# Output_Driver.net
KiCad netlist of a schematic drawn in Altium Designer
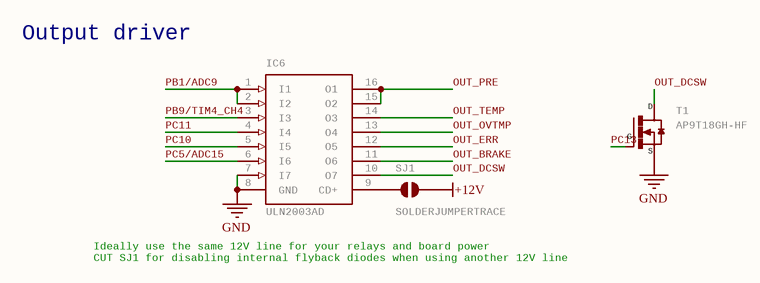
[diagram p0: Output Driver.SchDoc]

(export (version "E")
  (design (tool "Eeschema 10.0.6"))
  (components
    (comp (ref "IC6")
      (value "ULN2003AD")
      (footprint "SO16")
      (description "DRIVER ARRAY")
      (fields (field (name "LIBRARYNAME") "uln-udn"))
      (libsource (lib "Gate Driver Board") (part "ULN2003AD"))
    )
    (comp (ref "SJ1")
      (value "SOLDERJUMPERTRACE")
      (footprint "SJ_2S-TRACE")
      (libsource (lib "SparkFun-Passives") (part "SOLDERJUMPERTRACE"))
    )
    (comp (ref "T1")
      (value "AP9T18GH-HF")
      (footprint "D-PAK_TO252AA")
      (fields (field (name "D") "D") (field (name "S") "S") (field (name "G") "G"))
      (libsource (lib "Gate Driver Board") (part "AP9T18GH-HF"))
    )
  )
  (nets
    (net (code "1") (name "+12V") (class "Default")
      (node (ref "SJ1") (pin "2") (pinfunction "2_2") (pintype "passive"))
    )
    (net (code "2") (name "/OUT_BRAKE") (class "Default")
      (node (ref "IC6") (pin "11") (pinfunction "O6_11") (pintype "open_collector"))
    )
    (net (code "3") (name "/OUT_DCSW") (class "Default")
      (node (ref "IC6") (pin "10") (pinfunction "O7_10") (pintype "open_collector"))
      (node (ref "T1") (pin "4") (pinfunction "D_4") (pintype "passive"))
    )
    (net (code "4") (name "/OUT_ERR") (class "Default")
      (node (ref "IC6") (pin "12") (pinfunction "O5_12") (pintype "open_collector"))
    )
    (net (code "5") (name "/OUT_OVTMP") (class "Default")
      (node (ref "IC6") (pin "13") (pinfunction "O4_13") (pintype "open_collector"))
    )
    (net (code "6") (name "/OUT_PRE") (class "Default")
      (node (ref "IC6") (pin "15") (pinfunction "O2_15") (pintype "open_collector"))
      (node (ref "IC6") (pin "16") (pinfunction "O1_16") (pintype "open_collector"))
    )
    (net (code "7") (name "/OUT_TEMP") (class "Default")
      (node (ref "IC6") (pin "14") (pinfunction "O3_14") (pintype "open_collector"))
    )
    (net (code "8") (name "/PB1{slash}ADC9") (class "Default")
      (node (ref "IC6") (pin "1") (pinfunction "I1_1") (pintype "input"))
      (node (ref "IC6") (pin "2") (pinfunction "I2_2") (pintype "input"))
    )
    (net (code "9") (name "/PB9{slash}TIM4_CH4") (class "Default")
      (node (ref "IC6") (pin "3") (pinfunction "I3_3") (pintype "input"))
    )
    (net (code "10") (name "/PC5{slash}ADC15") (class "Default")
      (node (ref "IC6") (pin "6") (pinfunction "I6_6") (pintype "input"))
    )
    (net (code "11") (name "/PC10") (class "Default")
      (node (ref "IC6") (pin "5") (pinfunction "I5_5") (pintype "input"))
    )
    (net (code "12") (name "/PC11") (class "Default")
      (node (ref "IC6") (pin "4") (pinfunction "I4_4") (pintype "input"))
    )
    (net (code "13") (name "/PC13") (class "Default")
      (node (ref "T1") (pin "1") (pinfunction "G_1") (pintype "passive"))
    )
    (net (code "14") (name "GND") (class "Default")
      (node (ref "IC6") (pin "7") (pinfunction "I7_7") (pintype "input"))
      (node (ref "IC6") (pin "8") (pinfunction "GND_8") (pintype "power_in"))
      (node (ref "T1") (pin "3") (pinfunction "S_3") (pintype "passive"))
    )
    (net (code "15") (name "Net-(IC6-CD+)") (class "Default")
      (node (ref "IC6") (pin "9") (pinfunction "CD+_9") (pintype "passive"))
      (node (ref "SJ1") (pin "1") (pinfunction "1_1") (pintype "passive"))
    )
  )
)
